# Sensor.net
KiCad netlist of a schematic drawn in Altium Designer
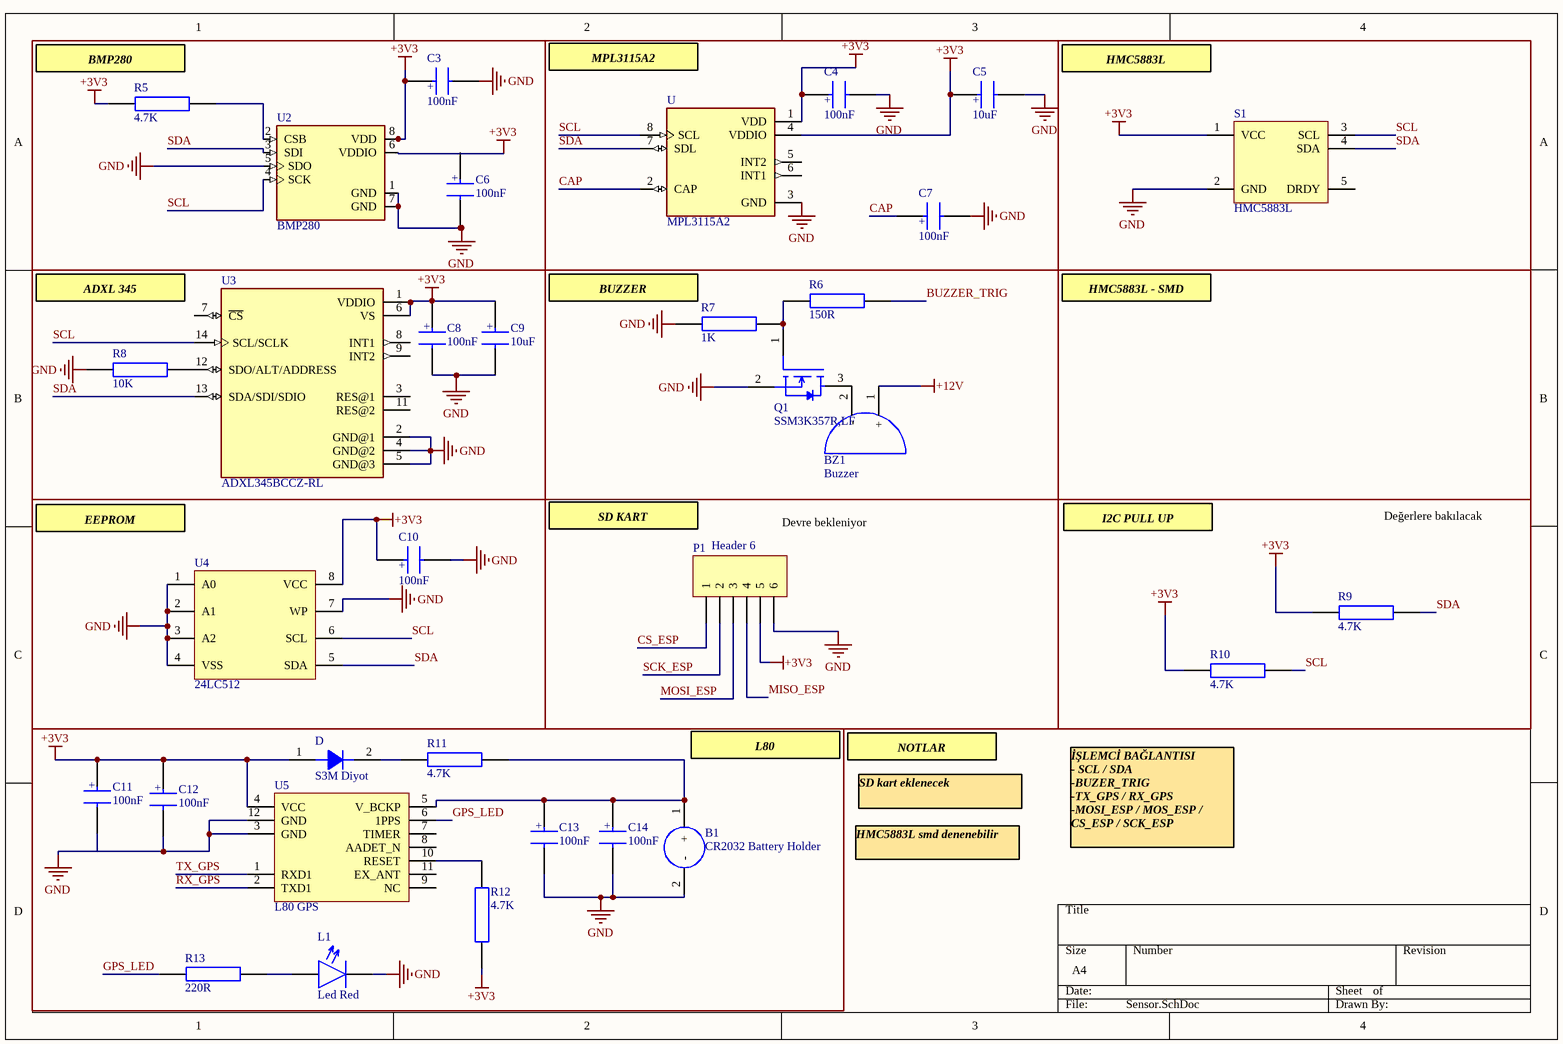
[diagram p0: Sensor.SchDoc]

(export (version "E")
  (design (tool "Eeschema 10.0.6"))
  (components
    (comp (ref "B1")
      (value "CR2032 Battery Holder")
      (footprint "CR2032")
      (description "Battery Holder")
      (libsource (lib "Udemy_Schlib1") (part "CR2032 Battery Holder"))
    )
    (comp (ref "BZ1")
      (value "Buzzer")
      (footprint "CMI-9605IC")
      (fields (field (name "DESIGNED BY") "Ahmet Azboy"))
      (libsource (lib "Udemy_Schlib1") (part "BUZZER"))
    )
    (comp (ref "C3")
      (value "100nF")
      (footprint "CAP_805")
      (description "0805 smd")
      (libsource (lib "Udemy_Schlib1") (part "CAP 1uF"))
    )
    (comp (ref "C4")
      (value "100nF")
      (footprint "CAP_805")
      (description "0805 smd")
      (libsource (lib "Udemy_Schlib1") (part "CAP 1uF"))
    )
    (comp (ref "C5")
      (value "10uF")
      (footprint "CAP_805")
      (description "0805 smd")
      (libsource (lib "Udemy_Schlib1") (part "CAP 1uF"))
    )
    (comp (ref "C6")
      (value "100nF")
      (footprint "CAP_805")
      (description "0805 smd")
      (libsource (lib "Udemy_Schlib1") (part "CAP 1uF"))
    )
    (comp (ref "C7")
      (value "100nF")
      (footprint "CAP_805")
      (description "0805 smd")
      (libsource (lib "Udemy_Schlib1") (part "CAP 1uF"))
    )
    (comp (ref "C8")
      (value "100nF")
      (footprint "CAP_805")
      (description "0805 smd")
      (libsource (lib "Udemy_Schlib1") (part "CAP 1uF"))
    )
    (comp (ref "C9")
      (value "10uF")
      (footprint "CAP_805")
      (description "0805 smd")
      (libsource (lib "Udemy_Schlib1") (part "CAP 1uF"))
    )
    (comp (ref "C10")
      (value "100nF")
      (footprint "CAP_805")
      (description "0805 smd")
      (libsource (lib "Udemy_Schlib1") (part "CAP 1uF"))
    )
    (comp (ref "C11")
      (value "100nF")
      (footprint "CAP_805")
      (description "0805 smd")
      (libsource (lib "Udemy_Schlib1") (part "CAP 1uF"))
    )
    (comp (ref "C12")
      (value "100nF")
      (footprint "CAP_805")
      (description "0805 smd")
      (libsource (lib "Udemy_Schlib1") (part "CAP 1uF"))
    )
    (comp (ref "C13")
      (value "100nF")
      (footprint "CAP_805")
      (description "0805 smd")
      (libsource (lib "Udemy_Schlib1") (part "CAP 1uF"))
    )
    (comp (ref "C14")
      (value "100nF")
      (footprint "CAP_805")
      (description "0805 smd")
      (libsource (lib "Udemy_Schlib1") (part "CAP 1uF"))
    )
    (comp (ref "D")
      (value "S3M Diyot")
      (footprint "DO214AA")
      (fields (field (name "VOLTAGE") "1000V"))
      (libsource (lib "Udemy_Schlib1") (part "S3M Diyot"))
    )
    (comp (ref "L1")
      (value "Led Red")
      (footprint "Led 1206")
      (libsource (lib "Udemy_Schlib1") (part "Led Red"))
    )
    (comp (ref "P1")
      (value "Header 6")
      (footprint "HDR1X6")
      (description "Header, 6-Pin")
      (fields (field (name "PUBLISHER") "Altium Limited"))
      (libsource (lib "Miscellaneous Connectors") (part "Header 6"))
    )
    (comp (ref "Q1")
      (value "SSM3K357R,LF")
      (footprint "SOT-23F")
      (description "Trans MOSFET N-CH Si 60V 0.65A Automotive 3-Pin SOT-23F T/R")
      (fields (field (name "MANUFACTURER") "Toshiba") (field (name "DESIGNED BY") "Ahmet Azboy"))
      (libsource (lib "Udemy_Schlib1") (part "SSM3K357R,LF"))
    )
    (comp (ref "R5")
      (value "4.7K")
      (footprint "RES_1206")
      (libsource (lib "Udemy_Schlib1") (part "RES 1K 1206"))
    )
    (comp (ref "R6")
      (value "150R")
      (footprint "RES_1206")
      (libsource (lib "Udemy_Schlib1") (part "RES 1K 1206"))
    )
    (comp (ref "R7")
      (value "1K")
      (footprint "RES_1206")
      (libsource (lib "Udemy_Schlib1") (part "RES 1K 1206"))
    )
    (comp (ref "R8")
      (value "10K")
      (footprint "RES_1206")
      (libsource (lib "Udemy_Schlib1") (part "RES 1K 1206"))
    )
    (comp (ref "R9")
      (value "4.7K")
      (footprint "RES_1206")
      (libsource (lib "Udemy_Schlib1") (part "RES 1K 1206"))
    )
    (comp (ref "R10")
      (value "4.7K")
      (footprint "RES_1206")
      (libsource (lib "Udemy_Schlib1") (part "RES 1K 1206"))
    )
    (comp (ref "R11")
      (value "4.7K")
      (footprint "RES_1206")
      (libsource (lib "Udemy_Schlib1") (part "RES 1K 1206"))
    )
    (comp (ref "R12")
      (value "4.7K")
      (footprint "RES_1206")
      (libsource (lib "Udemy_Schlib1") (part "RES 1K 1206"))
    )
    (comp (ref "R13")
      (value "220R")
      (footprint "RES_1206")
      (libsource (lib "Udemy_Schlib1") (part "RES 1K 1206"))
    )
    (comp (ref "S1")
      (value "HMC5883L")
      (footprint "HMC5883L")
      (description "Üç Eksenli Manyometre sensörü")
      (libsource (lib "Udemy_Schlib1") (part "HMC5883L"))
    )
    (comp (ref "U")
      (value "MPL3115A2")
      (footprint "PSON125P300X500X120-8N")
      (description "Pressure Sensor 7.25PSI ~ 15.95PSI _50kPa ~ 110kPa_ Absolute 24 b 8-TLGA")
      (fields (field (name "MF") "NXP USA"))
      (libsource (lib "Schlib") (part "MPL3115A2"))
    )
    (comp (ref "U2")
      (value "BMP280")
      (footprint "XDCR_BMP280")
      (description "BMP280 Absolute Barometric Pressure Sensor for Battery Powered Devices 2 x 2.5mm")
      (libsource (lib "Schlib") (part "BMP280"))
    )
    (comp (ref "U3")
      (value "ADXL345BCCZ-RL")
      (footprint "PQFN80P300X500X79-14N")
      (description "Accelerometer X, Y, Z Axis Â±2g, 4g, 8g, 16g 0.05Hz ~ 1.6kHz 14-LGA (3x5)")
      (fields (field (name "MF") "Analog Devices"))
      (libsource (lib "Schlib") (part "ADXL345BCCZ-RL"))
    )
    (comp (ref "U4")
      (value "24LC512")
      (footprint "soic-8")
      (description "EEPROM Serial-2Wire 512K-bit 64K x 8 3.3V/5V 8-Pin SOIJ Tube / IC EEPROM 512KBIT 400KHZ 8SOIJ")
      (fields
        (field (name "MANUFACTURER") "Microchip")
        (field (name "MANUFACTURER PART NUMBER") "24LC512-I/SM")
        (field (name "DESIGNED BY") "Ahmet Azboy")
      )
      (libsource (lib "Udemy_Schlib1") (part "24LC512"))
    )
    (comp (ref "U5")
      (value "L80 GPS")
      (footprint "L-80")
      (fields (field (name "DESIGNED BY") "Ahmet Azboy"))
      (libsource (lib "Udemy_Schlib1") (part "L80 GPS"))
    )
  )
  (nets
    (net (code "1") (name "+3V3") (class "Default")
      (node (ref "C10") (pin "1") (pinfunction "1_1") (pintype "passive"))
      (node (ref "C11") (pin "1") (pinfunction "1_1") (pintype "passive"))
      (node (ref "C12") (pin "1") (pinfunction "1_1") (pintype "passive"))
      (node (ref "C3") (pin "1") (pinfunction "1_1") (pintype "passive"))
      (node (ref "C4") (pin "1") (pinfunction "1_1") (pintype "passive"))
      (node (ref "C5") (pin "1") (pinfunction "1_1") (pintype "passive"))
      (node (ref "C8") (pin "1") (pinfunction "1_1") (pintype "passive"))
      (node (ref "C9") (pin "1") (pinfunction "1_1") (pintype "passive"))
      (node (ref "D") (pin "1") (pintype "passive"))
      (node (ref "P1") (pin "5") (pinfunction "5_5") (pintype "passive"))
      (node (ref "R10") (pin "1") (pintype "passive"))
      (node (ref "R12") (pin "2") (pintype "passive"))
      (node (ref "R5") (pin "1") (pintype "passive"))
      (node (ref "R9") (pin "1") (pintype "passive"))
      (node (ref "S1") (pin "1") (pinfunction "VCC_1") (pintype "passive"))
      (node (ref "U") (pin "1") (pinfunction "VDD_1") (pintype "power_in"))
      (node (ref "U") (pin "4") (pinfunction "VDDIO_4") (pintype "power_in"))
      (node (ref "U2") (pin "6") (pinfunction "VDDIO_6") (pintype "power_in"))
      (node (ref "U2") (pin "8") (pinfunction "VDD_8") (pintype "power_in"))
      (node (ref "U3") (pin "1") (pinfunction "VDDIO_1") (pintype "power_in"))
      (node (ref "U3") (pin "6") (pinfunction "VS_6") (pintype "power_in"))
      (node (ref "U4") (pin "8") (pinfunction "__VCC_8") (pintype "passive"))
      (node (ref "U5") (pin "4") (pinfunction "VCC_4") (pintype "passive"))
    )
    (net (code "2") (name "+12V") (class "Default")
      (node (ref "BZ1") (pin "1") (pinfunction "+_1") (pintype "passive"))
    )
    (net (code "3") (name "/BUZZER_TRIG") (class "Default") (node (ref "R6") (pin "2") (pintype "passive")))
    (net (code "4") (name "/CAP") (class "Default")
      (node (ref "C7") (pin "1") (pinfunction "1_1") (pintype "passive"))
      (node (ref "U") (pin "2") (pinfunction "CAP_2") (pintype "bidirectional"))
    )
    (net (code "5") (name "/CS_ESP") (class "Default")
      (node (ref "P1") (pin "1") (pinfunction "1_1") (pintype "passive"))
    )
    (net (code "6") (name "/GPS_LED") (class "Default")
      (node (ref "R13") (pin "1") (pintype "passive"))
      (node (ref "U5") (pin "6") (pinfunction "1PPS_6") (pintype "passive"))
    )
    (net (code "7") (name "/MISO_ESP") (class "Default")
      (node (ref "P1") (pin "4") (pinfunction "4_4") (pintype "passive"))
    )
    (net (code "8") (name "/MOSI_ESP") (class "Default")
      (node (ref "P1") (pin "3") (pinfunction "3_3") (pintype "passive"))
    )
    (net (code "9") (name "/RX_GPS") (class "Default")
      (node (ref "U5") (pin "2") (pinfunction "TXD1_2") (pintype "passive"))
    )
    (net (code "10") (name "/SCK_ESP") (class "Default")
      (node (ref "P1") (pin "2") (pinfunction "2_2") (pintype "passive"))
    )
    (net (code "11") (name "/SCL") (class "Default")
      (node (ref "R10") (pin "2") (pintype "passive"))
      (node (ref "S1") (pin "3") (pinfunction "SCL_3") (pintype "passive"))
      (node (ref "U") (pin "8") (pinfunction "SCL_8") (pintype "input"))
      (node (ref "U2") (pin "4") (pinfunction "SCK_4") (pintype "input"))
      (node (ref "U3") (pin "14") (pinfunction "SCL/SCLK_14") (pintype "input"))
      (node (ref "U4") (pin "6") (pinfunction "SCL_6") (pintype "passive"))
    )
    (net (code "12") (name "/SDA") (class "Default")
      (node (ref "R9") (pin "2") (pintype "passive"))
      (node (ref "S1") (pin "4") (pinfunction "SDA_4") (pintype "passive"))
      (node (ref "U") (pin "7") (pinfunction "SDL_7") (pintype "bidirectional"))
      (node (ref "U2") (pin "3") (pinfunction "SDI_3") (pintype "input"))
      (node (ref "U3") (pin "13") (pinfunction "SDA/SDI/SDIO_13") (pintype "bidirectional"))
      (node (ref "U4") (pin "5") (pinfunction "SDA_5") (pintype "passive"))
    )
    (net (code "13") (name "/TX_GPS") (class "Default")
      (node (ref "U5") (pin "1") (pinfunction "RXD1_1") (pintype "passive"))
    )
    (net (code "14") (name "GND") (class "Default")
      (node (ref "B1") (pin "2") (pinfunction "-_2") (pintype "passive"))
      (node (ref "C10") (pin "2") (pinfunction "2_2") (pintype "passive"))
      (node (ref "C12") (pin "2") (pinfunction "2_2") (pintype "passive"))
      (node (ref "C13") (pin "2") (pinfunction "2_2") (pintype "passive"))
      (node (ref "C14") (pin "2") (pinfunction "2_2") (pintype "passive"))
      (node (ref "C3") (pin "2") (pinfunction "2_2") (pintype "passive"))
      (node (ref "C4") (pin "2") (pinfunction "2_2") (pintype "passive"))
      (node (ref "C5") (pin "2") (pinfunction "2_2") (pintype "passive"))
      (node (ref "C6") (pin "2") (pinfunction "2_2") (pintype "passive"))
      (node (ref "C7") (pin "2") (pinfunction "2_2") (pintype "passive"))
      (node (ref "C8") (pin "2") (pinfunction "2_2") (pintype "passive"))
      (node (ref "C9") (pin "2") (pinfunction "2_2") (pintype "passive"))
      (node (ref "L1") (pin "2") (pintype "passive"))
      (node (ref "P1") (pin "6") (pinfunction "6_6") (pintype "passive"))
      (node (ref "Q1") (pin "2") (pinfunction "S_2") (pintype "passive"))
      (node (ref "R7") (pin "1") (pintype "passive"))
      (node (ref "R8") (pin "1") (pintype "passive"))
      (node (ref "S1") (pin "2") (pinfunction "GND_2") (pintype "passive"))
      (node (ref "U") (pin "3") (pinfunction "GND_3") (pintype "power_in"))
      (node (ref "U2") (pin "1") (pinfunction "GND_1") (pintype "power_in"))
      (node (ref "U2") (pin "5") (pinfunction "SDO_5") (pintype "input"))
      (node (ref "U2") (pin "7") (pinfunction "GND_7") (pintype "power_in"))
      (node (ref "U3") (pin "2") (pinfunction "GND@1_2") (pintype "power_in"))
      (node (ref "U3") (pin "4") (pinfunction "GND@2_4") (pintype "power_in"))
      (node (ref "U3") (pin "5") (pinfunction "GND@3_5") (pintype "power_in"))
      (node (ref "U4") (pin "1") (pinfunction "A0_1") (pintype "passive"))
      (node (ref "U4") (pin "2") (pinfunction "A1_2") (pintype "passive"))
      (node (ref "U4") (pin "3") (pinfunction "A2_3") (pintype "passive"))
      (node (ref "U4") (pin "4") (pinfunction "VSS_4") (pintype "passive"))
      (node (ref "U4") (pin "7") (pinfunction "WP_7") (pintype "passive"))
      (node (ref "U5") (pin "12") (pinfunction "GND_12") (pintype "passive"))
      (node (ref "U5") (pin "3") (pinfunction "GND_3") (pintype "passive"))
    )
    (net (code "15") (name "Net-(B1-+)") (class "Default")
      (node (ref "B1") (pin "1") (pinfunction "+_1") (pintype "passive"))
      (node (ref "C13") (pin "1") (pinfunction "1_1") (pintype "passive"))
      (node (ref "C14") (pin "1") (pinfunction "1_1") (pintype "passive"))
      (node (ref "R11") (pin "2") (pintype "passive"))
      (node (ref "U5") (pin "5") (pinfunction "V_BCKP_5") (pintype "passive"))
    )
    (net (code "16") (name "Net-(BZ1--)") (class "Default")
      (node (ref "BZ1") (pin "2") (pinfunction "-_2") (pintype "passive"))
      (node (ref "Q1") (pin "3") (pinfunction "D_3") (pintype "passive"))
    )
    (net (code "17") (name "Net-(D-Pad2)") (class "Default")
      (node (ref "D") (pin "2") (pintype "passive"))
      (node (ref "R11") (pin "1") (pintype "passive"))
    )
    (net (code "18") (name "Net-(L1-Pad1)") (class "Default")
      (node (ref "L1") (pin "1") (pintype "passive"))
      (node (ref "R13") (pin "2") (pintype "passive"))
    )
    (net (code "19") (name "Net-(Q1-G)") (class "Default")
      (node (ref "Q1") (pin "1") (pinfunction "G_1") (pintype "passive"))
      (node (ref "R6") (pin "1") (pintype "passive"))
      (node (ref "R7") (pin "2") (pintype "passive"))
    )
    (net (code "20") (name "Net-(U2-CSB)") (class "Default")
      (node (ref "R5") (pin "2") (pintype "passive"))
      (node (ref "U2") (pin "2") (pinfunction "CSB_2") (pintype "input"))
    )
    (net (code "21") (name "Net-(U3-SDO{slash}ALT{slash}ADDRESS)") (class "Default")
      (node (ref "R8") (pin "2") (pintype "passive"))
      (node (ref "U3") (pin "12") (pinfunction "SDO/ALT/ADDRESS_12") (pintype "bidirectional"))
    )
    (net (code "22") (name "Net-(U5-RESET)") (class "Default")
      (node (ref "R12") (pin "1") (pintype "passive"))
      (node (ref "U5") (pin "10") (pinfunction "RESET_10") (pintype "passive"))
    )
    (net (code "23") (name "unconnected-(C6-Pad1)") (class "Default")
      (node (ref "C6") (pin "1") (pinfunction "1_1") (pintype "passive"))
    )
    (net (code "24") (name "unconnected-(C11-Pad2)") (class "Default")
      (node (ref "C11") (pin "2") (pinfunction "2_2") (pintype "passive"))
    )
    (net (code "25") (name "unconnected-(S1-DRDY-Pad5)") (class "Default")
      (node (ref "S1") (pin "5") (pinfunction "DRDY_5") (pintype "passive"))
    )
    (net (code "26") (name "unconnected-(U-INT1-Pad6)") (class "Default")
      (node (ref "U") (pin "6") (pinfunction "INT1_6") (pintype "output"))
    )
    (net (code "27") (name "unconnected-(U-INT2-Pad5)") (class "Default")
      (node (ref "U") (pin "5") (pinfunction "INT2_5") (pintype "output"))
    )
    (net (code "28") (name "unconnected-(U3-INT1-Pad8)") (class "Default")
      (node (ref "U3") (pin "8") (pinfunction "INT1_8") (pintype "output"))
    )
    (net (code "29") (name "unconnected-(U3-INT2-Pad9)") (class "Default")
      (node (ref "U3") (pin "9") (pinfunction "INT2_9") (pintype "output"))
    )
    (net (code "30") (name "unconnected-(U3-RES@1-Pad3)") (class "Default")
      (node (ref "U3") (pin "3") (pinfunction "RES@1_3") (pintype "passive"))
    )
    (net (code "31") (name "unconnected-(U3-RES@2-Pad11)") (class "Default")
      (node (ref "U3") (pin "11") (pinfunction "RES@2_11") (pintype "passive"))
    )
    (net (code "32") (name "unconnected-(U3-~{CS}-Pad7)") (class "Default")
      (node (ref "U3") (pin "7") (pinfunction "~{CS}_7") (pintype "bidirectional"))
    )
    (net (code "33") (name "unconnected-(U5-AADET_N-Pad8)") (class "Default")
      (node (ref "U5") (pin "8") (pinfunction "AADET_N_8") (pintype "passive"))
    )
    (net (code "34") (name "unconnected-(U5-EX_ANT-Pad11)") (class "Default")
      (node (ref "U5") (pin "11") (pinfunction "EX_ANT_11") (pintype "passive"))
    )
    (net (code "35") (name "unconnected-(U5-NC-Pad9)") (class "Default")
      (node (ref "U5") (pin "9") (pinfunction "NC_9") (pintype "passive"))
    )
    (net (code "36") (name "unconnected-(U5-TIMER-Pad7)") (class "Default")
      (node (ref "U5") (pin "7") (pinfunction "TIMER_7") (pintype "passive"))
    )
  )
)
